# FPGA_HEADER.net
KiCad netlist of a schematic drawn in Altium Designer
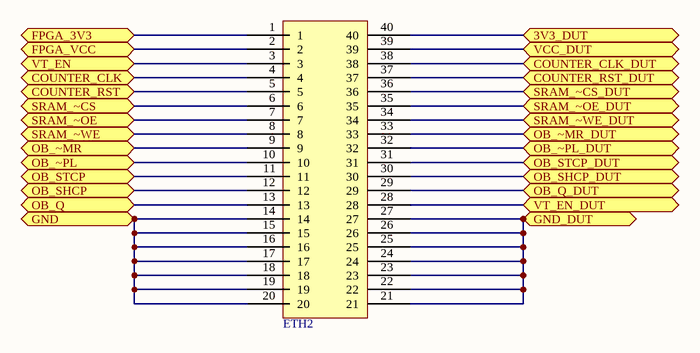
[diagram p0: FPGA_HEADER.SchDoc]

(export (version "E")
  (design (tool "Eeschema 10.0.6"))
  (components
    (comp (ref "ETH2")
      (value "ADAFRUIT_HEADER")
      (footprint "FEMALE_HEADER_SMD")
      (description "Extra tall female header (SMD)")
      (libsource (lib "DUTBoard") (part "ADAFRUIT_HEADER"))
    )
  )
  (nets
    (net (code "1") (name "/3V3_DUT") (class "Default")
      (node (ref "ETH2") (pin "40") (pinfunction "40_40") (pintype "passive"))
    )
    (net (code "2") (name "/COUNTER_CLK") (class "Default")
      (node (ref "ETH2") (pin "4") (pinfunction "4_4") (pintype "passive"))
    )
    (net (code "3") (name "/COUNTER_CLK_DUT") (class "Default")
      (node (ref "ETH2") (pin "38") (pinfunction "38_38") (pintype "passive"))
    )
    (net (code "4") (name "/COUNTER_RST") (class "Default")
      (node (ref "ETH2") (pin "5") (pinfunction "5_5") (pintype "passive"))
    )
    (net (code "5") (name "/COUNTER_RST_DUT") (class "Default")
      (node (ref "ETH2") (pin "37") (pinfunction "37_37") (pintype "passive"))
    )
    (net (code "6") (name "/FPGA_3V3") (class "Default")
      (node (ref "ETH2") (pin "1") (pinfunction "1_1") (pintype "passive"))
    )
    (net (code "7") (name "/FPGA_VCC") (class "Default")
      (node (ref "ETH2") (pin "2") (pinfunction "2_2") (pintype "passive"))
    )
    (net (code "8") (name "/GND") (class "Default")
      (node (ref "ETH2") (pin "14") (pinfunction "14_14") (pintype "passive"))
      (node (ref "ETH2") (pin "15") (pinfunction "15_15") (pintype "passive"))
      (node (ref "ETH2") (pin "16") (pinfunction "16_16") (pintype "passive"))
      (node (ref "ETH2") (pin "17") (pinfunction "17_17") (pintype "passive"))
      (node (ref "ETH2") (pin "18") (pinfunction "18_18") (pintype "passive"))
      (node (ref "ETH2") (pin "19") (pinfunction "19_19") (pintype "passive"))
      (node (ref "ETH2") (pin "20") (pinfunction "20_20") (pintype "passive"))
    )
    (net (code "9") (name "/GND_DUT") (class "Default")
      (node (ref "ETH2") (pin "21") (pinfunction "21_21") (pintype "passive"))
      (node (ref "ETH2") (pin "22") (pinfunction "22_22") (pintype "passive"))
      (node (ref "ETH2") (pin "23") (pinfunction "23_23") (pintype "passive"))
      (node (ref "ETH2") (pin "24") (pinfunction "24_24") (pintype "passive"))
      (node (ref "ETH2") (pin "25") (pinfunction "25_25") (pintype "passive"))
      (node (ref "ETH2") (pin "26") (pinfunction "26_26") (pintype "passive"))
      (node (ref "ETH2") (pin "27") (pinfunction "27_27") (pintype "passive"))
    )
    (net (code "10") (name "/OB_Q") (class "Default")
      (node (ref "ETH2") (pin "13") (pinfunction "13_13") (pintype "passive"))
    )
    (net (code "11") (name "/OB_Q_DUT") (class "Default")
      (node (ref "ETH2") (pin "29") (pinfunction "29_29") (pintype "passive"))
    )
    (net (code "12") (name "/OB_SHCP") (class "Default")
      (node (ref "ETH2") (pin "12") (pinfunction "12_12") (pintype "passive"))
    )
    (net (code "13") (name "/OB_SHCP_DUT") (class "Default")
      (node (ref "ETH2") (pin "30") (pinfunction "30_30") (pintype "passive"))
    )
    (net (code "14") (name "/OB_STCP") (class "Default")
      (node (ref "ETH2") (pin "11") (pinfunction "11_11") (pintype "passive"))
    )
    (net (code "15") (name "/OB_STCP_DUT") (class "Default")
      (node (ref "ETH2") (pin "31") (pinfunction "31_31") (pintype "passive"))
    )
    (net (code "16") (name "/OB_~MR") (class "Default")
      (node (ref "ETH2") (pin "9") (pinfunction "9_9") (pintype "passive"))
    )
    (net (code "17") (name "/OB_~MR_DUT") (class "Default")
      (node (ref "ETH2") (pin "33") (pinfunction "33_33") (pintype "passive"))
    )
    (net (code "18") (name "/OB_~PL") (class "Default")
      (node (ref "ETH2") (pin "10") (pinfunction "10_10") (pintype "passive"))
    )
    (net (code "19") (name "/OB_~PL_DUT") (class "Default")
      (node (ref "ETH2") (pin "32") (pinfunction "32_32") (pintype "passive"))
    )
    (net (code "20") (name "/SRAM_~CS") (class "Default")
      (node (ref "ETH2") (pin "6") (pinfunction "6_6") (pintype "passive"))
    )
    (net (code "21") (name "/SRAM_~CS_DUT") (class "Default")
      (node (ref "ETH2") (pin "36") (pinfunction "36_36") (pintype "passive"))
    )
    (net (code "22") (name "/SRAM_~OE") (class "Default")
      (node (ref "ETH2") (pin "7") (pinfunction "7_7") (pintype "passive"))
    )
    (net (code "23") (name "/SRAM_~OE_DUT") (class "Default")
      (node (ref "ETH2") (pin "35") (pinfunction "35_35") (pintype "passive"))
    )
    (net (code "24") (name "/SRAM_~WE") (class "Default")
      (node (ref "ETH2") (pin "8") (pinfunction "8_8") (pintype "passive"))
    )
    (net (code "25") (name "/SRAM_~WE_DUT") (class "Default")
      (node (ref "ETH2") (pin "34") (pinfunction "34_34") (pintype "passive"))
    )
    (net (code "26") (name "/VCC_DUT") (class "Default")
      (node (ref "ETH2") (pin "39") (pinfunction "39_39") (pintype "passive"))
    )
    (net (code "27") (name "/VT_EN") (class "Default")
      (node (ref "ETH2") (pin "3") (pinfunction "3_3") (pintype "passive"))
    )
    (net (code "28") (name "/VT_EN_DUT") (class "Default")
      (node (ref "ETH2") (pin "28") (pinfunction "28_28") (pintype "passive"))
    )
  )
)
